# MesschieberV5_1.net
KiCad netlist of a schematic drawn in EAGLE
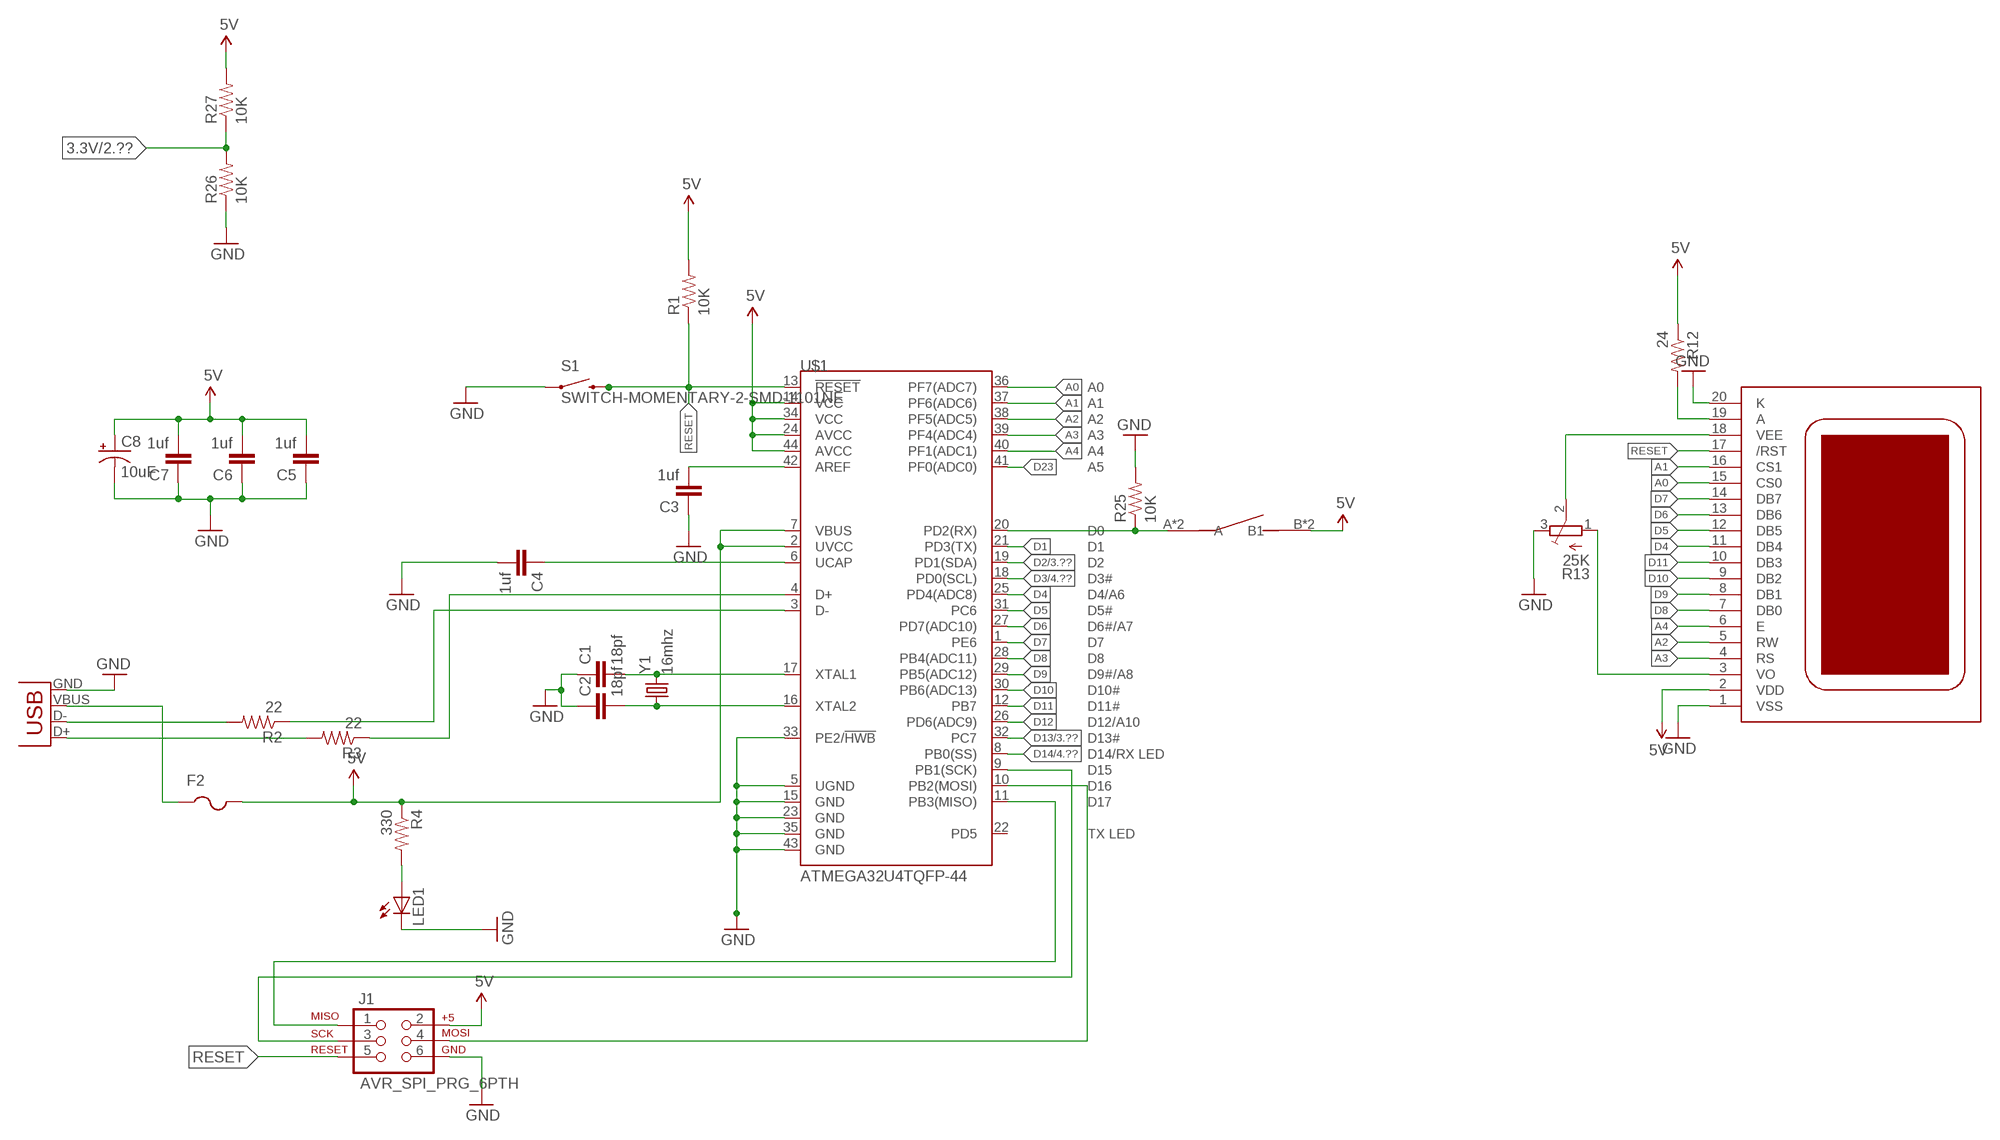
[diagram p0: schematic, sheet 1]
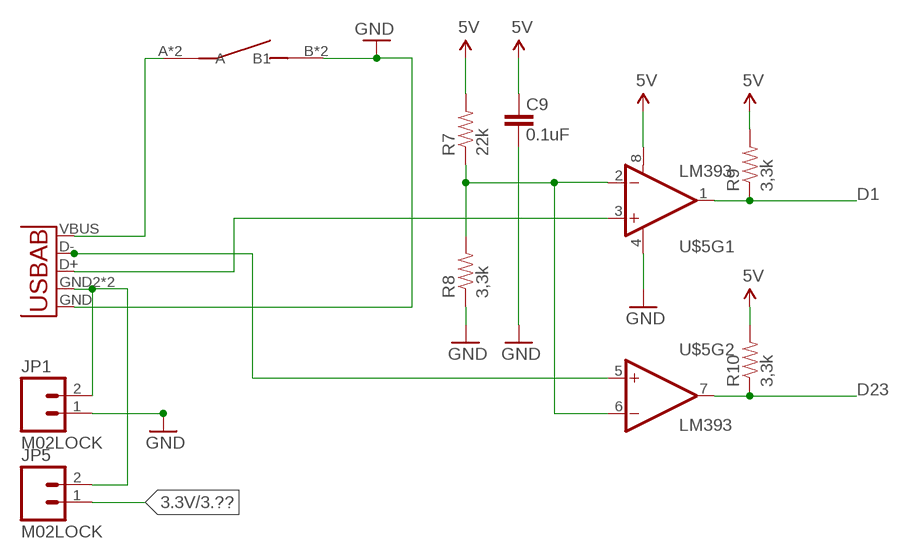
[diagram p1: schematic, sheet 2]
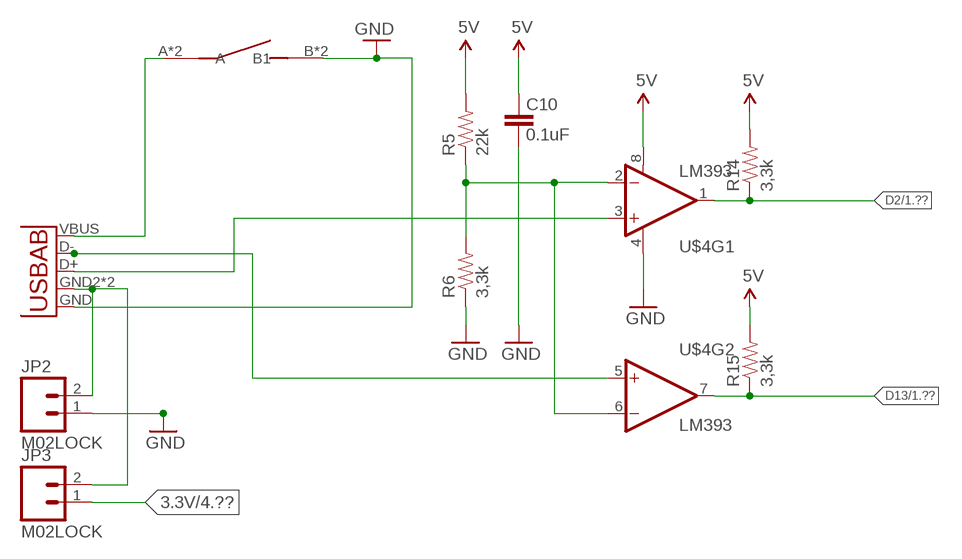
[diagram p2: schematic, sheet 3]
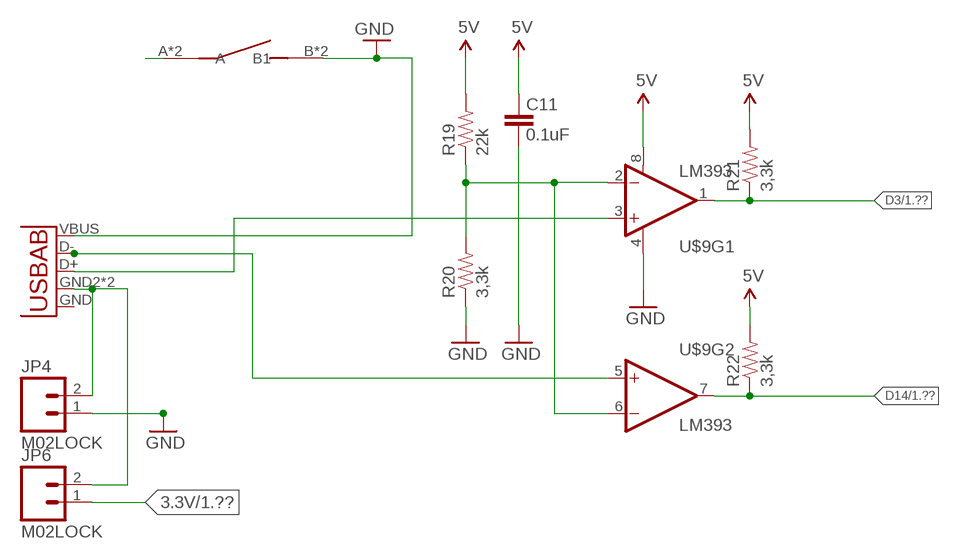
[diagram p3: schematic, sheet 4]

(export (version "E")
  (design (tool "Eeschema 10.0.6"))
  (components
    (comp (ref "C1")
      (value "18pf")
      (footprint "eagle-import:0805")
      (libsource (lib "eagle-import") (part "SparkFun-Capacitors_CAP0805"))
    )
    (comp (ref "C2")
      (value "18pf")
      (footprint "eagle-import:0805")
      (libsource (lib "eagle-import") (part "SparkFun-Capacitors_CAP0805"))
    )
    (comp (ref "C3")
      (value "1uf")
      (footprint "eagle-import:0805")
      (libsource (lib "eagle-import") (part "SparkFun-Capacitors_CAP0805"))
    )
    (comp (ref "C4")
      (value "1uf")
      (footprint "eagle-import:0805")
      (libsource (lib "eagle-import") (part "SparkFun-Capacitors_CAP0805"))
    )
    (comp (ref "C5")
      (value "1uf")
      (footprint "eagle-import:0805")
      (libsource (lib "eagle-import") (part "SparkFun-Capacitors_CAP0805"))
    )
    (comp (ref "C6")
      (value "1uf")
      (footprint "eagle-import:0805")
      (libsource (lib "eagle-import") (part "SparkFun-Capacitors_CAP0805"))
    )
    (comp (ref "C7")
      (value "1uf")
      (footprint "eagle-import:0805")
      (libsource (lib "eagle-import") (part "SparkFun-Capacitors_CAP0805"))
    )
    (comp (ref "C8")
      (value "10uF")
      (footprint "eagle-import:EIA3528")
      (libsource (lib "eagle-import") (part "10UF-20V-10%(TANT)"))
    )
    (comp (ref "F2")
      (value "PTCFUSE-1812")
      (footprint "eagle-import:1812")
      (libsource (lib "eagle-import") (part "PTCFUSE-1812"))
    )
    (comp (ref "J1")
      (value "AVR_SPI_PRG_6PTH")
      (footprint "eagle-import:2X3")
      (libsource (lib "eagle-import") (part "AVR_SPI_PRG_6PTH"))
    )
    (comp (ref "JP7")
      (value "USB-SMD-NS")
      (footprint "eagle-import:USB-MINIB-NOSTOP")
      (libsource (lib "eagle-import") (part "USB-SMD-NS"))
    )
    (comp (ref "LED1")
      (value "LEDSML0805")
      (footprint "eagle-import:SML0805")
      (libsource (lib "eagle-import") (part "LEDSML0805"))
    )
    (comp (ref "R1")
      (value "10K")
      (footprint "eagle-import:0603")
      (libsource (lib "eagle-import") (part "RESISTOR0603"))
    )
    (comp (ref "R2")
      (value "22")
      (footprint "eagle-import:0603")
      (libsource (lib "eagle-import") (part "RESISTOR0603"))
    )
    (comp (ref "R3")
      (value "22")
      (footprint "eagle-import:0603")
      (libsource (lib "eagle-import") (part "RESISTOR0603"))
    )
    (comp (ref "R4")
      (value "330")
      (footprint "eagle-import:0603")
      (libsource (lib "eagle-import") (part "RESISTOR0603"))
    )
    (comp (ref "R12")
      (value "24")
      (footprint "eagle-import:0603")
      (libsource (lib "eagle-import") (part "RESISTOR0603"))
    )
    (comp (ref "R13")
      (value "25K")
      (footprint "eagle-import:SM-42_43A")
      (libsource (lib "eagle-import") (part "TRIM_EU-SM-42/43A"))
    )
    (comp (ref "R25")
      (value "10K")
      (footprint "eagle-import:0603")
      (libsource (lib "eagle-import") (part "RESISTOR0603"))
    )
    (comp (ref "R26")
      (value "10K")
      (footprint "eagle-import:0805")
      (libsource (lib "eagle-import") (part "RESISTOR"))
    )
    (comp (ref "R27")
      (value "10K")
      (footprint "eagle-import:0805")
      (libsource (lib "eagle-import") (part "RESISTOR"))
    )
    (comp (ref "S1")
      (value "SWITCH-MOMENTARY-2-SMD-1101NE")
      (footprint "eagle-import:TACTILE-SWITCH-1101NE")
      (libsource (lib "eagle-import") (part "SWITCH-MOMENTARY-2-SMD-1101NE"))
    )
    (comp (ref "U$1")
      (value "ATMEGA32U4TQFP-44")
      (footprint "eagle-import:TQFP44")
      (libsource (lib "eagle-import") (part "ATMEGA32U4TQFP-44"))
    )
    (comp (ref "U$2")
      (value "TS12864A")
      (footprint "eagle-import:TS12864")
      (libsource (lib "eagle-import") (part "TS12864A"))
    )
    (comp (ref "U$12")
      (value "TASTE_R3FTL6")
      (footprint "eagle-import:TASTE_R3FTL6")
      (libsource (lib "eagle-import") (part "TASTE_R3FTL6"))
    )
    (comp (ref "Y1")
      (value "16mhz")
      (footprint "eagle-import:CRYSTAL-SMD-5X3")
      (libsource (lib "eagle-import") (part "CRYSTAL5X3"))
    )
    (comp (ref "C11")
      (value "0.1uF")
      (footprint "eagle-import:0805")
      (libsource (lib "eagle-import") (part "CAP0805"))
    )
    (comp (ref "JP4")
      (value "M02LOCK")
      (footprint "eagle-import:1X02_LOCK")
      (libsource (lib "eagle-import") (part "M02LOCK"))
    )
    (comp (ref "JP6")
      (value "M02LOCK")
      (footprint "eagle-import:1X02_LOCK")
      (libsource (lib "eagle-import") (part "M02LOCK"))
    )
    (comp (ref "R19")
      (value "22k")
      (footprint "eagle-import:0603")
      (libsource (lib "eagle-import") (part "RESISTOR0603"))
    )
    (comp (ref "R20")
      (value "3,3k")
      (footprint "eagle-import:0603")
      (libsource (lib "eagle-import") (part "RESISTOR0603"))
    )
    (comp (ref "R21")
      (value "3,3k")
      (footprint "eagle-import:0603")
      (libsource (lib "eagle-import") (part "RESISTOR0603"))
    )
    (comp (ref "R22")
      (value "3,3k")
      (footprint "eagle-import:0603")
      (libsource (lib "eagle-import") (part "RESISTOR0603"))
    )
    (comp (ref "U$9")
      (value "LM393")
      (footprint "eagle-import:SO08")
      (libsource (lib "eagle-import") (part "LM393"))
    )
    (comp (ref "U$10")
      (value "USB-A")
      (footprint "eagle-import:USB-A")
      (libsource (lib "eagle-import") (part "USB-A"))
    )
    (comp (ref "U$11")
      (value "TASTE_R3FTL6")
      (footprint "eagle-import:TASTE_R3FTL6")
      (libsource (lib "eagle-import") (part "TASTE_R3FTL6"))
    )
    (comp (ref "C10")
      (value "0.1uF")
      (footprint "eagle-import:0805")
      (libsource (lib "eagle-import") (part "CAP0805"))
    )
    (comp (ref "JP2")
      (value "M02LOCK")
      (footprint "eagle-import:1X02_LOCK")
      (libsource (lib "eagle-import") (part "M02LOCK"))
    )
    (comp (ref "JP3")
      (value "M02LOCK")
      (footprint "eagle-import:1X02_LOCK")
      (libsource (lib "eagle-import") (part "M02LOCK"))
    )
    (comp (ref "R5")
      (value "22k")
      (footprint "eagle-import:0603")
      (libsource (lib "eagle-import") (part "RESISTOR0603"))
    )
    (comp (ref "R6")
      (value "3,3k")
      (footprint "eagle-import:0603")
      (libsource (lib "eagle-import") (part "RESISTOR0603"))
    )
    (comp (ref "R14")
      (value "3,3k")
      (footprint "eagle-import:0603")
      (libsource (lib "eagle-import") (part "RESISTOR0603"))
    )
    (comp (ref "R15")
      (value "3,3k")
      (footprint "eagle-import:0603")
      (libsource (lib "eagle-import") (part "RESISTOR0603"))
    )
    (comp (ref "U$4")
      (value "LM393")
      (footprint "eagle-import:SO08")
      (libsource (lib "eagle-import") (part "LM393"))
    )
    (comp (ref "U$6")
      (value "USB-A")
      (footprint "eagle-import:USB-A")
      (libsource (lib "eagle-import") (part "USB-A"))
    )
    (comp (ref "U$8")
      (value "TASTE_R3FTL6")
      (footprint "eagle-import:TASTE_R3FTL6")
      (libsource (lib "eagle-import") (part "TASTE_R3FTL6"))
    )
    (comp (ref "C9")
      (value "0.1uF")
      (footprint "eagle-import:0805")
      (libsource (lib "eagle-import") (part "CAP0805"))
    )
    (comp (ref "JP1")
      (value "M02LOCK")
      (footprint "eagle-import:1X02_LOCK")
      (libsource (lib "eagle-import") (part "M02LOCK"))
    )
    (comp (ref "JP5")
      (value "M02LOCK")
      (footprint "eagle-import:1X02_LOCK")
      (libsource (lib "eagle-import") (part "M02LOCK"))
    )
    (comp (ref "R7")
      (value "22k")
      (footprint "eagle-import:0603")
      (libsource (lib "eagle-import") (part "RESISTOR0603"))
    )
    (comp (ref "R8")
      (value "3,3k")
      (footprint "eagle-import:0603")
      (libsource (lib "eagle-import") (part "RESISTOR0603"))
    )
    (comp (ref "R9")
      (value "3,3k")
      (footprint "eagle-import:0603")
      (libsource (lib "eagle-import") (part "RESISTOR0603"))
    )
    (comp (ref "R10")
      (value "3,3k")
      (footprint "eagle-import:0603")
      (libsource (lib "eagle-import") (part "RESISTOR0603"))
    )
    (comp (ref "U$3")
      (value "TASTE_R3FTL6")
      (footprint "eagle-import:TASTE_R3FTL6")
      (libsource (lib "eagle-import") (part "TASTE_R3FTL6"))
    )
    (comp (ref "U$5")
      (value "LM393")
      (footprint "eagle-import:SO08")
      (libsource (lib "eagle-import") (part "LM393"))
    )
    (comp (ref "U$7")
      (value "USB-A")
      (footprint "eagle-import:USB-A")
      (libsource (lib "eagle-import") (part "USB-A"))
    )
  )
  (nets
    (net (code "1") (name "3.3V") (class "Default")
      (node (ref "JP3") (pin "1") (pinfunction "1_1") (pintype "passive"))
      (node (ref "JP5") (pin "1") (pinfunction "1_1") (pintype "passive"))
      (node (ref "JP6") (pin "1") (pinfunction "1_1") (pintype "passive"))
      (node (ref "R26") (pin "2") (pinfunction "2_2") (pintype "passive"))
      (node (ref "R27") (pin "1") (pinfunction "1_1") (pintype "passive"))
    )
    (net (code "2") (name "5V") (class "Default")
      (node (ref "C10") (pin "2") (pinfunction "2_2") (pintype "passive"))
      (node (ref "C11") (pin "2") (pinfunction "2_2") (pintype "passive"))
      (node (ref "C5") (pin "2") (pinfunction "2_2") (pintype "passive"))
      (node (ref "C6") (pin "2") (pinfunction "2_2") (pintype "passive"))
      (node (ref "C7") (pin "2") (pinfunction "2_2") (pintype "passive"))
      (node (ref "C8") (pin "A") (pinfunction "+_A") (pintype "passive"))
      (node (ref "C9") (pin "2") (pinfunction "2_2") (pintype "passive"))
      (node (ref "F2") (pin "2") (pinfunction "2_2") (pintype "passive"))
      (node (ref "J1") (pin "2") (pinfunction "2_2") (pintype "passive"))
      (node (ref "R1") (pin "2") (pinfunction "2_2") (pintype "passive"))
      (node (ref "R10") (pin "2") (pinfunction "2_2") (pintype "passive"))
      (node (ref "R12") (pin "1") (pinfunction "1_1") (pintype "passive"))
      (node (ref "R14") (pin "2") (pinfunction "2_2") (pintype "passive"))
      (node (ref "R15") (pin "2") (pinfunction "2_2") (pintype "passive"))
      (node (ref "R19") (pin "2") (pinfunction "2_2") (pintype "passive"))
      (node (ref "R21") (pin "2") (pinfunction "2_2") (pintype "passive"))
      (node (ref "R22") (pin "2") (pinfunction "2_2") (pintype "passive"))
      (node (ref "R27") (pin "2") (pinfunction "2_2") (pintype "passive"))
      (node (ref "R4") (pin "1") (pinfunction "1_1") (pintype "passive"))
      (node (ref "R5") (pin "2") (pinfunction "2_2") (pintype "passive"))
      (node (ref "R7") (pin "2") (pinfunction "2_2") (pintype "passive"))
      (node (ref "R9") (pin "2") (pinfunction "2_2") (pintype "passive"))
      (node (ref "U$1") (pin "14") (pinfunction "VCC_14") (pintype "bidirectional"))
      (node (ref "U$1") (pin "2") (pinfunction "UVCC_2") (pintype "bidirectional"))
      (node (ref "U$1") (pin "24") (pinfunction "AVCC_24") (pintype "bidirectional"))
      (node (ref "U$1") (pin "34") (pinfunction "VCC_34") (pintype "bidirectional"))
      (node (ref "U$1") (pin "44") (pinfunction "AVCC_44") (pintype "bidirectional"))
      (node (ref "U$1") (pin "7") (pinfunction "VBUS_7") (pintype "bidirectional"))
      (node (ref "U$12") (pin "B") (pinfunction "B1_B") (pintype "bidirectional"))
      (node (ref "U$12") (pin "B1") (pinfunction "B1_B1") (pintype "bidirectional"))
      (node (ref "U$2") (pin "2") (pinfunction "VDD_2") (pintype "power_in"))
      (node (ref "U$4") (pin "8") (pinfunction "V+_8") (pintype "power_in"))
      (node (ref "U$5") (pin "8") (pinfunction "V+_8") (pintype "power_in"))
      (node (ref "U$9") (pin "8") (pinfunction "V+_8") (pintype "power_in"))
    )
    (net (code "3") (name "A0") (class "Default")
      (node (ref "U$1") (pin "36") (pinfunction "PF7(ADC7)_36") (pintype "bidirectional"))
      (node (ref "U$2") (pin "15") (pinfunction "CS0_15") (pintype "input"))
    )
    (net (code "4") (name "A1") (class "Default")
      (node (ref "U$1") (pin "37") (pinfunction "PF6(ADC6)_37") (pintype "bidirectional"))
      (node (ref "U$2") (pin "16") (pinfunction "CS1_16") (pintype "input"))
    )
    (net (code "5") (name "A2") (class "Default")
      (node (ref "U$1") (pin "38") (pinfunction "PF5(ADC5)_38") (pintype "bidirectional"))
      (node (ref "U$2") (pin "5") (pinfunction "RW_5") (pintype "input"))
    )
    (net (code "6") (name "A3") (class "Default")
      (node (ref "U$1") (pin "39") (pinfunction "PF4(ADC4)_39") (pintype "bidirectional"))
      (node (ref "U$2") (pin "4") (pinfunction "RS_4") (pintype "input"))
    )
    (net (code "7") (name "A4") (class "Default")
      (node (ref "U$1") (pin "40") (pinfunction "PF1(ADC1)_40") (pintype "bidirectional"))
      (node (ref "U$2") (pin "6") (pinfunction "E_6") (pintype "input"))
    )
    (net (code "8") (name "D1") (class "Default")
      (node (ref "R9") (pin "1") (pinfunction "1_1") (pintype "passive"))
      (node (ref "U$1") (pin "21") (pinfunction "PD3(TX)_21") (pintype "bidirectional"))
      (node (ref "U$5") (pin "1") (pinfunction "OUT_1") (pintype "output"))
    )
    (net (code "9") (name "D2") (class "Default")
      (node (ref "R14") (pin "1") (pinfunction "1_1") (pintype "passive"))
      (node (ref "U$1") (pin "19") (pinfunction "PD1(SDA)_19") (pintype "bidirectional"))
      (node (ref "U$4") (pin "1") (pinfunction "OUT_1") (pintype "output"))
    )
    (net (code "10") (name "D3") (class "Default")
      (node (ref "R21") (pin "1") (pinfunction "1_1") (pintype "passive"))
      (node (ref "U$1") (pin "18") (pinfunction "PD0(SCL)_18") (pintype "bidirectional"))
      (node (ref "U$9") (pin "1") (pinfunction "OUT_1") (pintype "output"))
    )
    (net (code "11") (name "D4") (class "Default")
      (node (ref "U$1") (pin "25") (pinfunction "PD4(ADC8)_25") (pintype "bidirectional"))
      (node (ref "U$2") (pin "11") (pinfunction "DB4_11") (pintype "bidirectional"))
    )
    (net (code "12") (name "D5") (class "Default")
      (node (ref "U$1") (pin "31") (pinfunction "PC6_31") (pintype "bidirectional"))
      (node (ref "U$2") (pin "12") (pinfunction "DB5_12") (pintype "bidirectional"))
    )
    (net (code "13") (name "D6") (class "Default")
      (node (ref "U$1") (pin "27") (pinfunction "PD7(ADC10)_27") (pintype "bidirectional"))
      (node (ref "U$2") (pin "13") (pinfunction "DB6_13") (pintype "bidirectional"))
    )
    (net (code "14") (name "D7") (class "Default")
      (node (ref "U$1") (pin "1") (pinfunction "PE6_1") (pintype "bidirectional"))
      (node (ref "U$2") (pin "14") (pinfunction "DB7_14") (pintype "bidirectional"))
    )
    (net (code "15") (name "D8") (class "Default")
      (node (ref "U$1") (pin "28") (pinfunction "PB4(ADC11)_28") (pintype "bidirectional"))
      (node (ref "U$2") (pin "7") (pinfunction "DB0_7") (pintype "bidirectional"))
    )
    (net (code "16") (name "D9") (class "Default")
      (node (ref "U$1") (pin "29") (pinfunction "PB5(ADC12)_29") (pintype "bidirectional"))
      (node (ref "U$2") (pin "8") (pinfunction "DB1_8") (pintype "bidirectional"))
    )
    (net (code "17") (name "D10") (class "Default")
      (node (ref "U$1") (pin "30") (pinfunction "PB6(ADC13)_30") (pintype "bidirectional"))
      (node (ref "U$2") (pin "9") (pinfunction "DB2_9") (pintype "bidirectional"))
    )
    (net (code "18") (name "D11") (class "Default")
      (node (ref "U$1") (pin "12") (pinfunction "PB7_12") (pintype "bidirectional"))
      (node (ref "U$2") (pin "10") (pinfunction "DB3_10") (pintype "bidirectional"))
    )
    (net (code "19") (name "D12") (class "Default")
      (node (ref "U$1") (pin "26") (pinfunction "PD6(ADC9)_26") (pintype "bidirectional"))
    )
    (net (code "20") (name "D13") (class "Default")
      (node (ref "R15") (pin "1") (pinfunction "1_1") (pintype "passive"))
      (node (ref "U$1") (pin "32") (pinfunction "PC7_32") (pintype "bidirectional"))
      (node (ref "U$4") (pin "7") (pinfunction "OUT_7") (pintype "output"))
    )
    (net (code "21") (name "D14") (class "Default")
      (node (ref "R22") (pin "1") (pinfunction "1_1") (pintype "passive"))
      (node (ref "U$1") (pin "8") (pinfunction "PB0(SS)_8") (pintype "bidirectional"))
      (node (ref "U$9") (pin "7") (pinfunction "OUT_7") (pintype "output"))
    )
    (net (code "22") (name "D23") (class "Default")
      (node (ref "R10") (pin "1") (pinfunction "1_1") (pintype "passive"))
      (node (ref "U$1") (pin "41") (pinfunction "PF0(ADC0)_41") (pintype "bidirectional"))
      (node (ref "U$5") (pin "7") (pinfunction "OUT_7") (pintype "output"))
    )
    (net (code "23") (name "GND") (class "Default")
      (node (ref "C1") (pin "1") (pinfunction "1_1") (pintype "passive"))
      (node (ref "C10") (pin "1") (pinfunction "1_1") (pintype "passive"))
      (node (ref "C11") (pin "1") (pinfunction "1_1") (pintype "passive"))
      (node (ref "C2") (pin "1") (pinfunction "1_1") (pintype "passive"))
      (node (ref "C3") (pin "1") (pinfunction "1_1") (pintype "passive"))
      (node (ref "C4") (pin "2") (pinfunction "2_2") (pintype "passive"))
      (node (ref "C5") (pin "1") (pinfunction "1_1") (pintype "passive"))
      (node (ref "C6") (pin "1") (pinfunction "1_1") (pintype "passive"))
      (node (ref "C7") (pin "1") (pinfunction "1_1") (pintype "passive"))
      (node (ref "C8") (pin "C") (pinfunction "-_C") (pintype "passive"))
      (node (ref "C9") (pin "1") (pinfunction "1_1") (pintype "passive"))
      (node (ref "J1") (pin "6") (pinfunction "6_6") (pintype "passive"))
      (node (ref "JP1") (pin "1") (pinfunction "1_1") (pintype "passive"))
      (node (ref "JP2") (pin "1") (pinfunction "1_1") (pintype "passive"))
      (node (ref "JP4") (pin "1") (pinfunction "1_1") (pintype "passive"))
      (node (ref "JP7") (pin "GND") (pinfunction "GND_GND") (pintype "bidirectional"))
      (node (ref "LED1") (pin "C") (pinfunction "C_C") (pintype "passive"))
      (node (ref "R13") (pin "3") (pinfunction "E_3") (pintype "passive"))
      (node (ref "R20") (pin "1") (pinfunction "1_1") (pintype "passive"))
      (node (ref "R25") (pin "2") (pinfunction "2_2") (pintype "passive"))
      (node (ref "R26") (pin "1") (pinfunction "1_1") (pintype "passive"))
      (node (ref "R6") (pin "1") (pinfunction "1_1") (pintype "passive"))
      (node (ref "R8") (pin "1") (pinfunction "1_1") (pintype "passive"))
      (node (ref "S1") (pin "P$1") (pinfunction "1_P$1") (pintype "passive"))
      (node (ref "U$1") (pin "15") (pinfunction "GND_15") (pintype "bidirectional"))
      (node (ref "U$1") (pin "23") (pinfunction "GND_23") (pintype "bidirectional"))
      (node (ref "U$1") (pin "33") (pinfunction "PE2/~{HWB}_33") (pintype "bidirectional"))
      (node (ref "U$1") (pin "35") (pinfunction "GND_35") (pintype "bidirectional"))
      (node (ref "U$1") (pin "43") (pinfunction "GND_43") (pintype "bidirectional"))
      (node (ref "U$1") (pin "5") (pinfunction "UGND_5") (pintype "bidirectional"))
      (node (ref "U$10") (pin "VBUS") (pinfunction "VBUS_VBUS") (pintype "bidirectional"))
      (node (ref "U$11") (pin "B") (pinfunction "B1_B") (pintype "bidirectional"))
      (node (ref "U$11") (pin "B1") (pinfunction "B1_B1") (pintype "bidirectional"))
      (node (ref "U$2") (pin "1") (pinfunction "VSS_1") (pintype "power_in"))
      (node (ref "U$2") (pin "20") (pinfunction "K_20") (pintype "input"))
      (node (ref "U$3") (pin "B") (pinfunction "B1_B") (pintype "bidirectional"))
      (node (ref "U$3") (pin "B1") (pinfunction "B1_B1") (pintype "bidirectional"))
      (node (ref "U$4") (pin "4") (pinfunction "V-_4") (pintype "power_in"))
      (node (ref "U$5") (pin "4") (pinfunction "V-_4") (pintype "power_in"))
      (node (ref "U$6") (pin "GND") (pinfunction "GND_GND") (pintype "bidirectional"))
      (node (ref "U$7") (pin "GND") (pinfunction "GND_GND") (pintype "bidirectional"))
      (node (ref "U$8") (pin "B") (pinfunction "B1_B") (pintype "bidirectional"))
      (node (ref "U$8") (pin "B1") (pinfunction "B1_B1") (pintype "bidirectional"))
      (node (ref "U$9") (pin "4") (pinfunction "V-_4") (pintype "power_in"))
    )
    (net (code "24") (name "Net-(F2-Pad1)") (class "Default")
      (node (ref "F2") (pin "1") (pinfunction "1_1") (pintype "passive"))
      (node (ref "JP7") (pin "VBUS") (pinfunction "VBUS_VBUS") (pintype "bidirectional"))
    )
    (net (code "25") (name "Net-(JP1-Pad2)") (class "Default")
      (node (ref "JP1") (pin "2") (pinfunction "2_2") (pintype "passive"))
      (node (ref "JP5") (pin "2") (pinfunction "2_2") (pintype "passive"))
      (node (ref "U$7") (pin "GND2") (pinfunction "USBID_GND2") (pintype "bidirectional"))
      (node (ref "U$7") (pin "GND3") (pinfunction "USBID_GND3") (pintype "bidirectional"))
    )
    (net (code "26") (name "Net-(JP2-Pad2)") (class "Default")
      (node (ref "JP2") (pin "2") (pinfunction "2_2") (pintype "passive"))
      (node (ref "JP3") (pin "2") (pinfunction "2_2") (pintype "passive"))
      (node (ref "U$6") (pin "GND2") (pinfunction "USBID_GND2") (pintype "bidirectional"))
      (node (ref "U$6") (pin "GND3") (pinfunction "USBID_GND3") (pintype "bidirectional"))
    )
    (net (code "27") (name "Net-(JP4-Pad2)") (class "Default")
      (node (ref "JP4") (pin "2") (pinfunction "2_2") (pintype "passive"))
      (node (ref "JP6") (pin "2") (pinfunction "2_2") (pintype "passive"))
      (node (ref "U$10") (pin "GND2") (pinfunction "USBID_GND2") (pintype "bidirectional"))
      (node (ref "U$10") (pin "GND3") (pinfunction "USBID_GND3") (pintype "bidirectional"))
    )
    (net (code "28") (name "Net-(JP7-PadD+)") (class "Default")
      (node (ref "JP7") (pin "D+") (pinfunction "D+_D+") (pintype "bidirectional"))
      (node (ref "R3") (pin "2") (pinfunction "2_2") (pintype "passive"))
    )
    (net (code "29") (name "Net-(JP7-PadD-)") (class "Default")
      (node (ref "JP7") (pin "D-") (pinfunction "D-_D-") (pintype "bidirectional"))
      (node (ref "R2") (pin "2") (pinfunction "2_2") (pintype "passive"))
    )
    (net (code "30") (name "Net-(LED1-PadA)") (class "Default")
      (node (ref "LED1") (pin "A") (pinfunction "A_A") (pintype "passive"))
      (node (ref "R4") (pin "2") (pinfunction "2_2") (pintype "passive"))
    )
    (net (code "31") (name "Net-(R13-A)") (class "Default")
      (node (ref "R13") (pin "1") (pinfunction "A_1") (pintype "passive"))
      (node (ref "U$2") (pin "3") (pinfunction "VO_3") (pintype "input"))
    )
    (net (code "32") (name "Net-(R13-S)") (class "Default")
      (node (ref "R13") (pin "2") (pinfunction "S_2") (pintype "passive"))
      (node (ref "U$2") (pin "18") (pinfunction "VEE_18") (pintype "power_in"))
    )
    (net (code "33") (name "Net-(U$1-AREF)") (class "Default")
      (node (ref "C3") (pin "2") (pinfunction "2_2") (pintype "passive"))
      (node (ref "U$1") (pin "42") (pinfunction "AREF_42") (pintype "bidirectional"))
    )
    (net (code "34") (name "Net-(U$1-D+)") (class "Default")
      (node (ref "R3") (pin "1") (pinfunction "1_1") (pintype "passive"))
      (node (ref "U$1") (pin "4") (pinfunction "D+_4") (pintype "bidirectional"))
    )
    (net (code "35") (name "Net-(U$1-D-)") (class "Default")
      (node (ref "R2") (pin "1") (pinfunction "1_1") (pintype "passive"))
      (node (ref "U$1") (pin "3") (pinfunction "D-_3") (pintype "bidirectional"))
    )
    (net (code "36") (name "Net-(U$1-PB1(SCK))") (class "Default")
      (node (ref "J1") (pin "3") (pinfunction "3_3") (pintype "passive"))
      (node (ref "U$1") (pin "9") (pinfunction "PB1(SCK)_9") (pintype "bidirectional"))
    )
    (net (code "37") (name "Net-(U$1-PB2(MOSI))") (class "Default")
      (node (ref "J1") (pin "4") (pinfunction "4_4") (pintype "passive"))
      (node (ref "U$1") (pin "10") (pinfunction "PB2(MOSI)_10") (pintype "bidirectional"))
    )
    (net (code "38") (name "Net-(U$1-PB3(MISO))") (class "Default")
      (node (ref "J1") (pin "1") (pinfunction "1_1") (pintype "passive"))
      (node (ref "U$1") (pin "11") (pinfunction "PB3(MISO)_11") (pintype "bidirectional"))
    )
    (net (code "39") (name "Net-(U$1-PD2(RX))") (class "Default")
      (node (ref "R25") (pin "1") (pinfunction "1_1") (pintype "passive"))
      (node (ref "U$1") (pin "20") (pinfunction "PD2(RX)_20") (pintype "bidirectional"))
      (node (ref "U$12") (pin "A") (pinfunction "A_A") (pintype "bidirectional"))
      (node (ref "U$12") (pin "A1") (pinfunction "A_A1") (pintype "bidirectional"))
    )
    (net (code "40") (name "Net-(U$1-UCAP)") (class "Default")
      (node (ref "C4") (pin "1") (pinfunction "1_1") (pintype "passive"))
      (node (ref "U$1") (pin "6") (pinfunction "UCAP_6") (pintype "bidirectional"))
    )
    (net (code "41") (name "Net-(U$1-XTAL1)") (class "Default")
      (node (ref "C1") (pin "2") (pinfunction "2_2") (pintype "passive"))
      (node (ref "U$1") (pin "17") (pinfunction "XTAL1_17") (pintype "bidirectional"))
      (node (ref "Y1") (pin "3") (pinfunction "2_3") (pintype "passive"))
    )
    (net (code "42") (name "Net-(U$1-XTAL2)") (class "Default")
      (node (ref "C2") (pin "2") (pinfunction "2_2") (pintype "passive"))
      (node (ref "U$1") (pin "16") (pinfunction "XTAL2_16") (pintype "bidirectional"))
      (node (ref "Y1") (pin "1") (pinfunction "1_1") (pintype "passive"))
    )
    (net (code "43") (name "Net-(U$2-A)") (class "Default")
      (node (ref "R12") (pin "2") (pinfunction "2_2") (pintype "passive"))
      (node (ref "U$2") (pin "19") (pinfunction "A_19") (pintype "power_in"))
    )
    (net (code "44") (name "Net-(U$3-A-PadA1)") (class "Default")
      (node (ref "U$3") (pin "A") (pinfunction "A_A") (pintype "bidirectional"))
      (node (ref "U$3") (pin "A1") (pinfunction "A_A1") (pintype "bidirectional"))
      (node (ref "U$7") (pin "VBUS") (pinfunction "VBUS_VBUS") (pintype "bidirectional"))
    )
    (net (code "45") (name "Net-(U$4A-+IN)") (class "Default")
      (node (ref "U$4") (pin "3") (pinfunction "+IN_3") (pintype "input"))
      (node (ref "U$6") (pin "D+") (pinfunction "D+_D+") (pintype "bidirectional"))
    )
    (net (code "46") (name "Net-(U$4A--IN)") (class "Default")
      (node (ref "R5") (pin "1") (pinfunction "1_1") (pintype "passive"))
      (node (ref "R6") (pin "2") (pinfunction "2_2") (pintype "passive"))
      (node (ref "U$4") (pin "2") (pinfunction "-IN_2") (pintype "input"))
      (node (ref "U$4") (pin "6") (pinfunction "-IN_6") (pintype "input"))
    )
    (net (code "47") (name "Net-(U$4B-+IN)") (class "Default")
      (node (ref "U$4") (pin "5") (pinfunction "+IN_5") (pintype "input"))
      (node (ref "U$6") (pin "D-") (pinfunction "D-_D-") (pintype "bidirectional"))
    )
    (net (code "48") (name "Net-(U$5A-+IN)") (class "Default")
      (node (ref "U$5") (pin "3") (pinfunction "+IN_3") (pintype "input"))
      (node (ref "U$7") (pin "D+") (pinfunction "D+_D+") (pintype "bidirectional"))
    )
    (net (code "49") (name "Net-(U$5A--IN)") (class "Default")
      (node (ref "R7") (pin "1") (pinfunction "1_1") (pintype "passive"))
      (node (ref "R8") (pin "2") (pinfunction "2_2") (pintype "passive"))
      (node (ref "U$5") (pin "2") (pinfunction "-IN_2") (pintype "input"))
      (node (ref "U$5") (pin "6") (pinfunction "-IN_6") (pintype "input"))
    )
    (net (code "50") (name "Net-(U$5B-+IN)") (class "Default")
      (node (ref "U$5") (pin "5") (pinfunction "+IN_5") (pintype "input"))
      (node (ref "U$7") (pin "D-") (pinfunction "D-_D-") (pintype "bidirectional"))
    )
    (net (code "51") (name "Net-(U$6-PadVBUS)") (class "Default")
      (node (ref "U$6") (pin "VBUS") (pinfunction "VBUS_VBUS") (pintype "bidirectional"))
      (node (ref "U$8") (pin "A") (pinfunction "A_A") (pintype "bidirectional"))
      (node (ref "U$8") (pin "A1") (pinfunction "A_A1") (pintype "bidirectional"))
    )
    (net (code "52") (name "Net-(U$9A-+IN)") (class "Default")
      (node (ref "U$10") (pin "D+") (pinfunction "D+_D+") (pintype "bidirectional"))
      (node (ref "U$9") (pin "3") (pinfunction "+IN_3") (pintype "input"))
    )
    (net (code "53") (name "Net-(U$9A--IN)") (class "Default")
      (node (ref "R19") (pin "1") (pinfunction "1_1") (pintype "passive"))
      (node (ref "R20") (pin "2") (pinfunction "2_2") (pintype "passive"))
      (node (ref "U$9") (pin "2") (pinfunction "-IN_2") (pintype "input"))
      (node (ref "U$9") (pin "6") (pinfunction "-IN_6") (pintype "input"))
    )
    (net (code "54") (name "Net-(U$9B-+IN)") (class "Default")
      (node (ref "U$10") (pin "D-") (pinfunction "D-_D-") (pintype "bidirectional"))
      (node (ref "U$9") (pin "5") (pinfunction "+IN_5") (pintype "input"))
    )
    (net (code "55") (name "Net-(U$11-A-PadA1)") (class "Default")
      (node (ref "U$11") (pin "A") (pinfunction "A_A") (pintype "bidirectional"))
      (node (ref "U$11") (pin "A1") (pinfunction "A_A1") (pintype "bidirectional"))
    )
    (net (code "56") (name "RESET") (class "Default")
      (node (ref "J1") (pin "5") (pinfunction "5_5") (pintype "passive"))
      (node (ref "R1") (pin "1") (pinfunction "1_1") (pintype "passive"))
      (node (ref "S1") (pin "P$2") (pinfunction "2_P$2") (pintype "passive"))
      (node (ref "U$1") (pin "13") (pinfunction "~{RESET}_13") (pintype "bidirectional"))
      (node (ref "U$2") (pin "17") (pinfunction "/RST_17") (pintype "input"))
    )
    (net (code "57") (name "unconnected-(U$1-PD5-Pad22)") (class "Default")
      (node (ref "U$1") (pin "22") (pinfunction "PD5_22") (pintype "bidirectional"))
    )
    (net (code "58") (name "unconnected-(U$10-PadGND)") (class "Default")
      (node (ref "U$10") (pin "GND") (pinfunction "GND_GND") (pintype "bidirectional"))
    )
  )
)
